# DIY-e-bike-thumb-throttle_v1.net
KiCad netlist of a schematic drawn in EAGLE
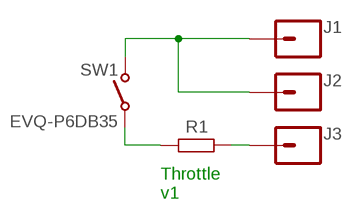
[diagram p0: schematic, sheet 1]

(export (version "E")
  (design (tool "Eeschema 10.0.6"))
  (components
    (comp (ref "J1")
      (value "M01SMD-4.5X1.5")
      (footprint "eagle-import:PAD-1.5X4.5")
      (libsource (lib "eagle-import") (part "M01SMD-4.5X1.5"))
    )
    (comp (ref "J2")
      (value "M01SMD-4.5X1.5")
      (footprint "eagle-import:PAD-1.5X4.5")
      (libsource (lib "eagle-import") (part "M01SMD-4.5X1.5"))
    )
    (comp (ref "J3")
      (value "M01SMD-4.5X1.5")
      (footprint "eagle-import:PAD-1.5X4.5")
      (libsource (lib "eagle-import") (part "M01SMD-4.5X1.5"))
    )
    (comp (ref "R1")
      (value "SMD-R-0603-SMALL")
      (footprint "eagle-import:0603-SMALL")
      (libsource (lib "eagle-import") (part "SMD-R-0603-SMALL"))
    )
    (comp (ref "SW1")
      (value "EVQ-P6DB35")
      (footprint "eagle-import:TACTILE_SWITCH_SMD-2")
      (libsource (lib "eagle-import") (part "TACTILE-IP68"))
    )
  )
  (nets
    (net (code "1") (name "Net-(J1-1)") (class "Default")
      (node (ref "J1") (pin "P$1") (pinfunction "1_P$1") (pintype "passive"))
      (node (ref "J2") (pin "P$1") (pinfunction "1_P$1") (pintype "passive"))
      (node (ref "SW1") (pin "1") (pinfunction "O_1") (pintype "passive"))
      (node (ref "SW1") (pin "4") (pinfunction "O_4") (pintype "passive"))
    )
    (net (code "2") (name "Net-(J3-1)") (class "Default")
      (node (ref "J3") (pin "P$1") (pinfunction "1_P$1") (pintype "passive"))
      (node (ref "R1") (pin "2") (pinfunction "2_2") (pintype "passive"))
    )
    (net (code "3") (name "Net-(R1-Pad1)") (class "Default")
      (node (ref "R1") (pin "1") (pinfunction "1_1") (pintype "passive"))
      (node (ref "SW1") (pin "2") (pinfunction "P_2") (pintype "passive"))
      (node (ref "SW1") (pin "3") (pinfunction "P_3") (pintype "passive"))
    )
  )
)
